# HumiTemp_V2.net
KiCad netlist of a schematic drawn in EAGLE
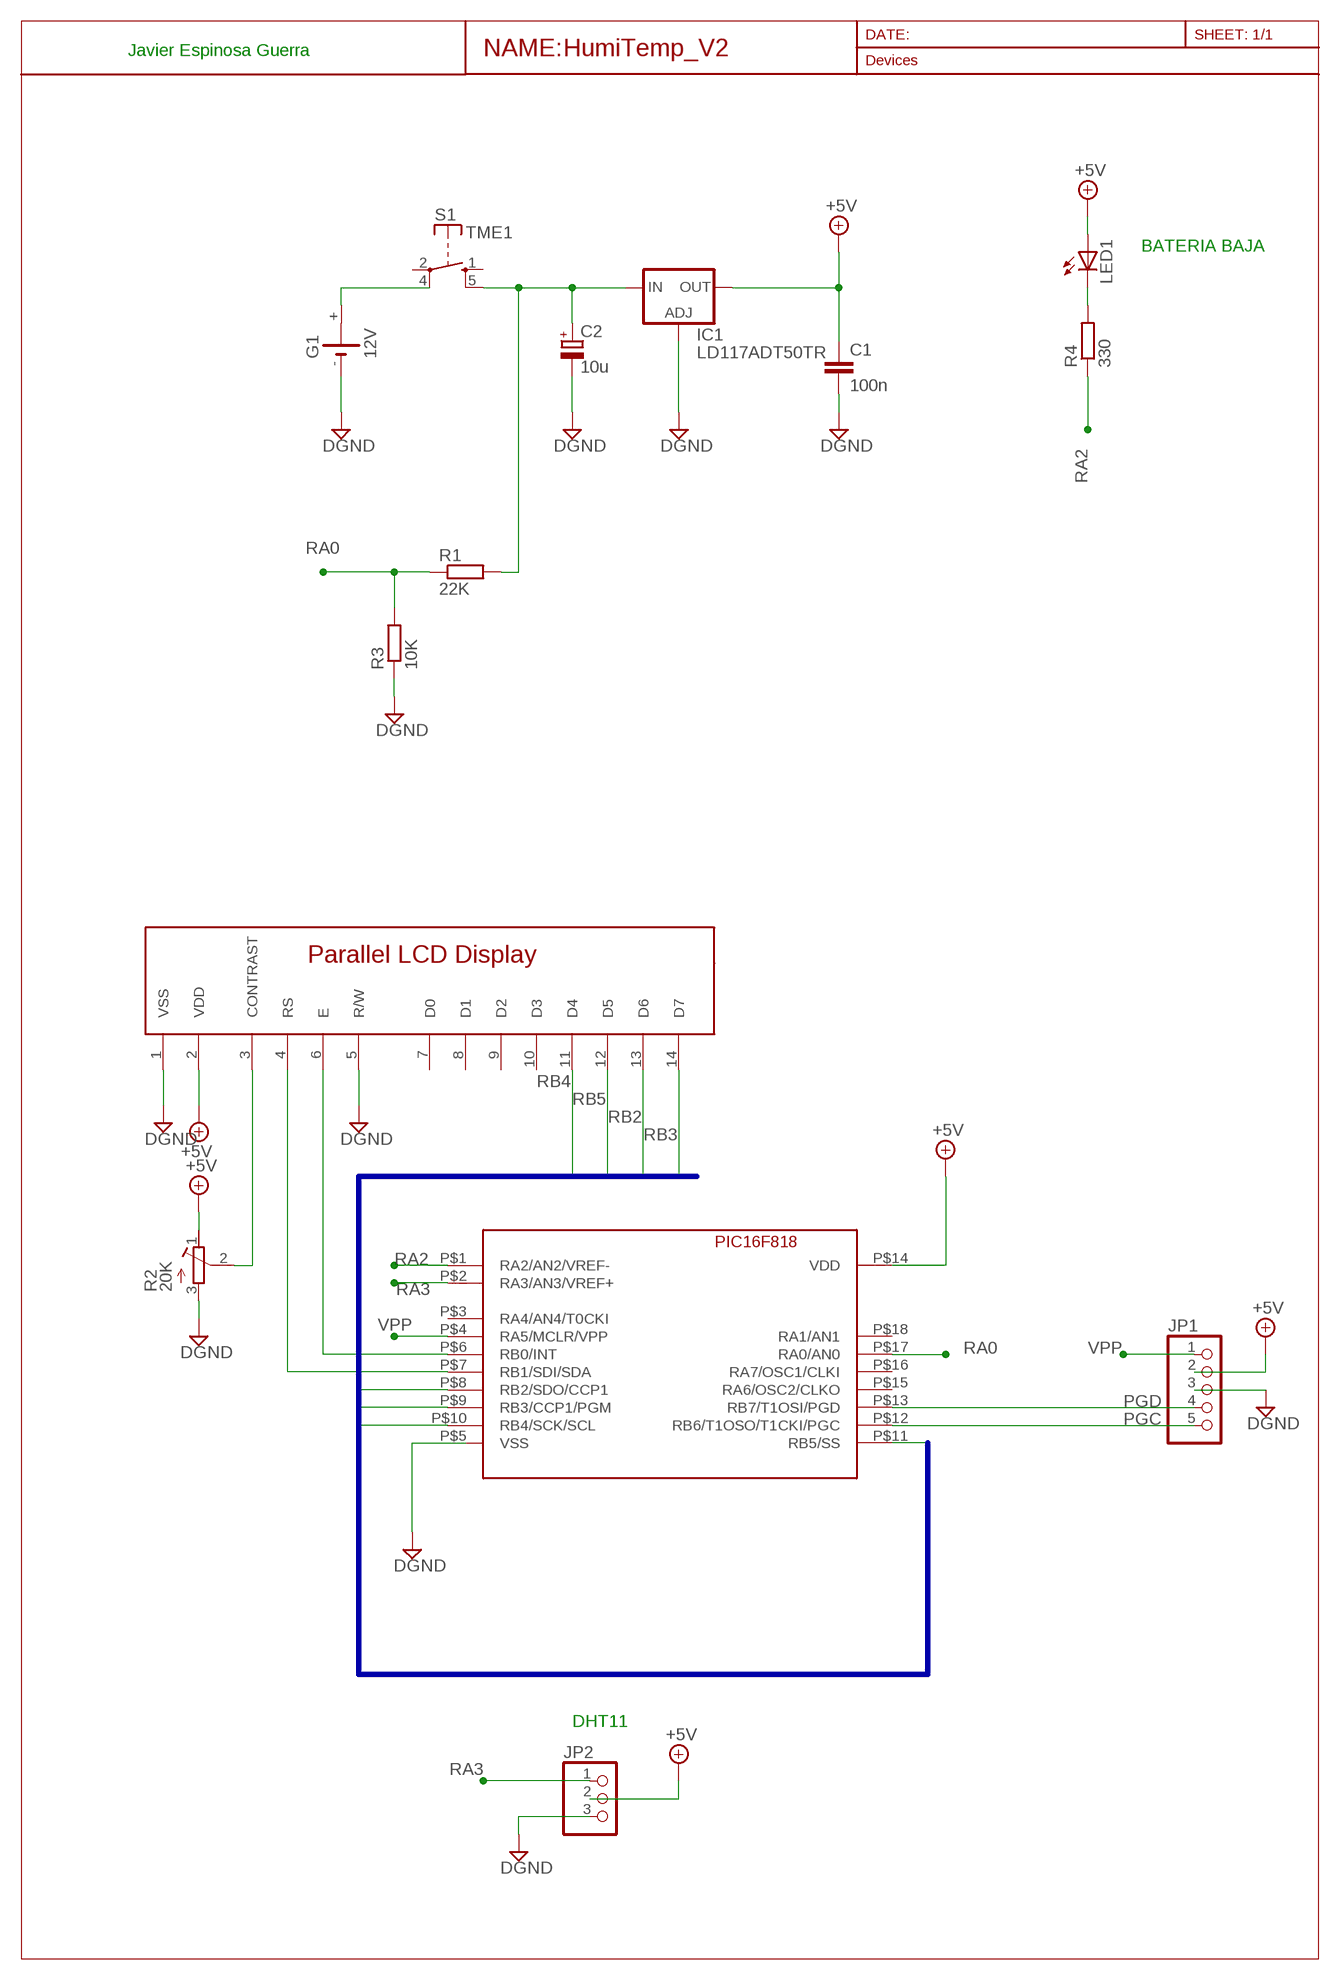
[diagram p0: schematic, sheet 1]

(export (version "E")
  (design (tool "Eeschema 10.0.6"))
  (components
    (comp (ref "C1")
      (value "100n")
      (footprint "eagle-import:C050-024X044")
      (libsource (lib "eagle-import") (part "C-EU050-024X044"))
    )
    (comp (ref "C2")
      (value "10u")
      (footprint "eagle-import:E2-4")
      (libsource (lib "eagle-import") (part "CPOL-EUE2-4"))
    )
    (comp (ref "G1")
      (value "12V")
      (footprint "eagle-import:CRAA")
      (libsource (lib "eagle-import") (part "CRAA"))
    )
    (comp (ref "IC1")
      (value "LD117ADT50TR")
      (footprint "eagle-import:DPACK")
      (libsource (lib "eagle-import") (part "LD117A?DT50TR"))
    )
    (comp (ref "JP1")
      (value "PINHD-1X5")
      (footprint "eagle-import:1X05")
      (libsource (lib "eagle-import") (part "PINHD-1X5"))
    )
    (comp (ref "JP2")
      (value "PINHD-1X3")
      (footprint "eagle-import:1X03")
      (libsource (lib "eagle-import") (part "PINHD-1X3"))
    )
    (comp (ref "LED1")
      (value "LED3MM")
      (footprint "eagle-import:LED3MM")
      (libsource (lib "eagle-import") (part "LED3MM"))
    )
    (comp (ref "PIC1")
      (value "PIC16F818")
      (footprint "eagle-import:PIC16F818")
      (libsource (lib "eagle-import") (part "PIC16F818"))
    )
    (comp (ref "R1")
      (value "22K")
      (footprint "eagle-import:R0805")
      (libsource (lib "eagle-import") (part "R-EU_R0805"))
    )
    (comp (ref "R2")
      (value "20K")
      (footprint "eagle-import:RTRIM43P")
      (libsource (lib "eagle-import") (part "R-TRIMM43P"))
    )
    (comp (ref "R3")
      (value "10K")
      (footprint "eagle-import:R0805")
      (libsource (lib "eagle-import") (part "R-EU_R0805"))
    )
    (comp (ref "R4")
      (value "330")
      (footprint "eagle-import:R0805")
      (libsource (lib "eagle-import") (part "R-EU_R0805"))
    )
    (comp (ref "S1")
      (value "TME1")
      (footprint "eagle-import:TME1")
      (libsource (lib "eagle-import") (part "TME1"))
    )
    (comp (ref "U$1")
      (value "PARALLEL_LCDSIP")
      (footprint "eagle-import:SIP_14")
      (libsource (lib "eagle-import") (part "PARALLEL_LCDSIP"))
    )
  )
  (nets
    (net (code "1") (name "+5V") (class "Default")
      (node (ref "C1") (pin "1") (pinfunction "1_1") (pintype "passive"))
      (node (ref "IC1") (pin "4") (pinfunction "OUT_4") (pintype "passive"))
      (node (ref "JP1") (pin "2") (pinfunction "2_2") (pintype "passive"))
      (node (ref "JP2") (pin "2") (pinfunction "2_2") (pintype "passive"))
      (node (ref "LED1") (pin "A") (pinfunction "A_A") (pintype "passive"))
      (node (ref "PIC1") (pin "P$14") (pinfunction "VDD_P$14") (pintype "bidirectional"))
      (node (ref "R2") (pin "1") (pinfunction "E_1") (pintype "passive"))
      (node (ref "U$1") (pin "2") (pinfunction "VDD_2") (pintype "bidirectional"))
    )
    (net (code "2") (name "/PGC") (class "Default")
      (node (ref "JP1") (pin "5") (pinfunction "5_5") (pintype "passive"))
      (node (ref "PIC1") (pin "P$12") (pinfunction "RB6/T1OSO/T1CKI/PGC_P$12") (pintype "bidirectional"))
    )
    (net (code "3") (name "/PGD") (class "Default")
      (node (ref "JP1") (pin "4") (pinfunction "4_4") (pintype "passive"))
      (node (ref "PIC1") (pin "P$13") (pinfunction "RB7/T1OSI/PGD_P$13") (pintype "bidirectional"))
    )
    (net (code "4") (name "/RA0") (class "Default")
      (node (ref "PIC1") (pin "P$17") (pinfunction "RA0/AN0_P$17") (pintype "bidirectional"))
      (node (ref "R1") (pin "1") (pinfunction "1_1") (pintype "passive"))
      (node (ref "R3") (pin "2") (pinfunction "2_2") (pintype "passive"))
    )
    (net (code "5") (name "/RA2") (class "Default")
      (node (ref "PIC1") (pin "P$1") (pinfunction "RA2/AN2/VREF-_P$1") (pintype "bidirectional"))
      (node (ref "R4") (pin "1") (pinfunction "1_1") (pintype "passive"))
    )
    (net (code "6") (name "/RA3") (class "Default")
      (node (ref "JP2") (pin "1") (pinfunction "1_1") (pintype "passive"))
      (node (ref "PIC1") (pin "P$2") (pinfunction "RA3/AN3/VREF+_P$2") (pintype "bidirectional"))
    )
    (net (code "7") (name "/RB2") (class "Default")
      (node (ref "U$1") (pin "13") (pinfunction "D6_13") (pintype "bidirectional"))
    )
    (net (code "8") (name "/RB3") (class "Default")
      (node (ref "U$1") (pin "14") (pinfunction "D7_14") (pintype "bidirectional"))
    )
    (net (code "9") (name "/RB4") (class "Default")
      (node (ref "U$1") (pin "11") (pinfunction "D4_11") (pintype "bidirectional"))
    )
    (net (code "10") (name "/RB5") (class "Default")
      (node (ref "U$1") (pin "12") (pinfunction "D5_12") (pintype "bidirectional"))
    )
    (net (code "11") (name "/VPP") (class "Default")
      (node (ref "JP1") (pin "1") (pinfunction "1_1") (pintype "passive"))
      (node (ref "PIC1") (pin "P$4") (pinfunction "RA5/MCLR/VPP_P$4") (pintype "bidirectional"))
    )
    (net (code "12") (name "DGND") (class "Default")
      (node (ref "C1") (pin "2") (pinfunction "2_2") (pintype "passive"))
      (node (ref "C2") (pin "-") (pinfunction "-_-") (pintype "passive"))
      (node (ref "G1") (pin "-") (pinfunction "-_-") (pintype "passive"))
      (node (ref "IC1") (pin "1") (pinfunction "ADJ_1") (pintype "input"))
      (node (ref "JP1") (pin "3") (pinfunction "3_3") (pintype "passive"))
      (node (ref "JP2") (pin "3") (pinfunction "3_3") (pintype "passive"))
      (node (ref "PIC1") (pin "P$5") (pinfunction "VSS_P$5") (pintype "bidirectional"))
      (node (ref "R2") (pin "3") (pinfunction "A_3") (pintype "passive"))
      (node (ref "R3") (pin "1") (pinfunction "1_1") (pintype "passive"))
      (node (ref "U$1") (pin "1") (pinfunction "VSS_1") (pintype "bidirectional"))
      (node (ref "U$1") (pin "5") (pinfunction "R/W_5") (pintype "bidirectional"))
    )
    (net (code "13") (name "Net-(G1-Pad+)") (class "Default")
      (node (ref "G1") (pin "+") (pinfunction "+_+") (pintype "passive"))
      (node (ref "S1") (pin "4") (pinfunction "P_4") (pintype "passive"))
    )
    (net (code "14") (name "Net-(IC1-IN)") (class "Default")
      (node (ref "C2") (pin "+") (pinfunction "+_+") (pintype "passive"))
      (node (ref "IC1") (pin "3") (pinfunction "IN_3") (pintype "input"))
      (node (ref "R1") (pin "2") (pinfunction "2_2") (pintype "passive"))
      (node (ref "S1") (pin "5") (pinfunction "S_5") (pintype "passive"))
    )
    (net (code "15") (name "Net-(LED1-C)") (class "Default")
      (node (ref "LED1") (pin "K") (pinfunction "C_K") (pintype "passive"))
      (node (ref "R4") (pin "2") (pinfunction "2_2") (pintype "passive"))
    )
    (net (code "16") (name "Net-(PIC1-RB0{slash}INT)") (class "Default")
      (node (ref "PIC1") (pin "P$6") (pinfunction "RB0/INT_P$6") (pintype "bidirectional"))
      (node (ref "U$1") (pin "6") (pinfunction "E_6") (pintype "bidirectional"))
    )
    (net (code "17") (name "Net-(PIC1-RB1{slash}SDI{slash}SDA)") (class "Default")
      (node (ref "PIC1") (pin "P$7") (pinfunction "RB1/SDI/SDA_P$7") (pintype "bidirectional"))
      (node (ref "U$1") (pin "4") (pinfunction "RS_4") (pintype "bidirectional"))
    )
    (net (code "18") (name "Net-(R2-S)") (class "Default")
      (node (ref "R2") (pin "2") (pinfunction "S_2") (pintype "passive"))
      (node (ref "U$1") (pin "3") (pinfunction "CONTRAST_3") (pintype "bidirectional"))
    )
    (net (code "19") (name "unconnected-(G1-+-Pad+@1)") (class "Default")
      (node (ref "G1") (pin "+@1") (pinfunction "+_+@1") (pintype "passive"))
    )
    (net (code "20") (name "unconnected-(PIC1-RA1{slash}AN1-PadP$18)") (class "Default")
      (node (ref "PIC1") (pin "P$18") (pinfunction "RA1/AN1_P$18") (pintype "bidirectional"))
    )
    (net (code "21") (name "unconnected-(PIC1-RA4{slash}AN4{slash}T0CKI-PadP$3)") (class "Default")
      (node (ref "PIC1") (pin "P$3") (pinfunction "RA4/AN4/T0CKI_P$3") (pintype "bidirectional"))
    )
    (net (code "22") (name "unconnected-(PIC1-RA6{slash}OSC2{slash}CLKO-PadP$15)") (class "Default")
      (node (ref "PIC1") (pin "P$15") (pinfunction "RA6/OSC2/CLKO_P$15") (pintype "bidirectional"))
    )
    (net (code "23") (name "unconnected-(PIC1-RA7{slash}OSC1{slash}CLKI-PadP$16)") (class "Default")
      (node (ref "PIC1") (pin "P$16") (pinfunction "RA7/OSC1/CLKI_P$16") (pintype "bidirectional"))
    )
    (net (code "24") (name "unconnected-(PIC1-RB2{slash}SDO{slash}CCP1-PadP$8)") (class "Default")
      (node (ref "PIC1") (pin "P$8") (pinfunction "RB2/SDO/CCP1_P$8") (pintype "bidirectional"))
    )
    (net (code "25") (name "unconnected-(PIC1-RB3{slash}CCP1{slash}PGM-PadP$9)") (class "Default")
      (node (ref "PIC1") (pin "P$9") (pinfunction "RB3/CCP1/PGM_P$9") (pintype "bidirectional"))
    )
    (net (code "26") (name "unconnected-(PIC1-RB4{slash}SCK{slash}SCL-PadP$10)") (class "Default")
      (node (ref "PIC1") (pin "P$10") (pinfunction "RB4/SCK/SCL_P$10") (pintype "bidirectional"))
    )
    (net (code "27") (name "unconnected-(PIC1-RB5{slash}SS-PadP$11)") (class "Default")
      (node (ref "PIC1") (pin "P$11") (pinfunction "RB5/SS_P$11") (pintype "bidirectional"))
    )
    (net (code "28") (name "unconnected-(S1-P-Pad2)") (class "Default")
      (node (ref "S1") (pin "2") (pinfunction "P_2") (pintype "passive"))
    )
    (net (code "29") (name "unconnected-(S1-S-Pad1)") (class "Default")
      (node (ref "S1") (pin "1") (pinfunction "S_1") (pintype "passive"))
    )
    (net (code "30") (name "unconnected-(U$1-D0-Pad7)") (class "Default")
      (node (ref "U$1") (pin "7") (pinfunction "D0_7") (pintype "bidirectional"))
    )
    (net (code "31") (name "unconnected-(U$1-D1-Pad8)") (class "Default")
      (node (ref "U$1") (pin "8") (pinfunction "D1_8") (pintype "bidirectional"))
    )
    (net (code "32") (name "unconnected-(U$1-D2-Pad9)") (class "Default")
      (node (ref "U$1") (pin "9") (pinfunction "D2_9") (pintype "bidirectional"))
    )
    (net (code "33") (name "unconnected-(U$1-D3-Pad10)") (class "Default")
      (node (ref "U$1") (pin "10") (pinfunction "D3_10") (pintype "bidirectional"))
    )
  )
)
